# Power.net
KiCad netlist of a schematic drawn in Altium Designer
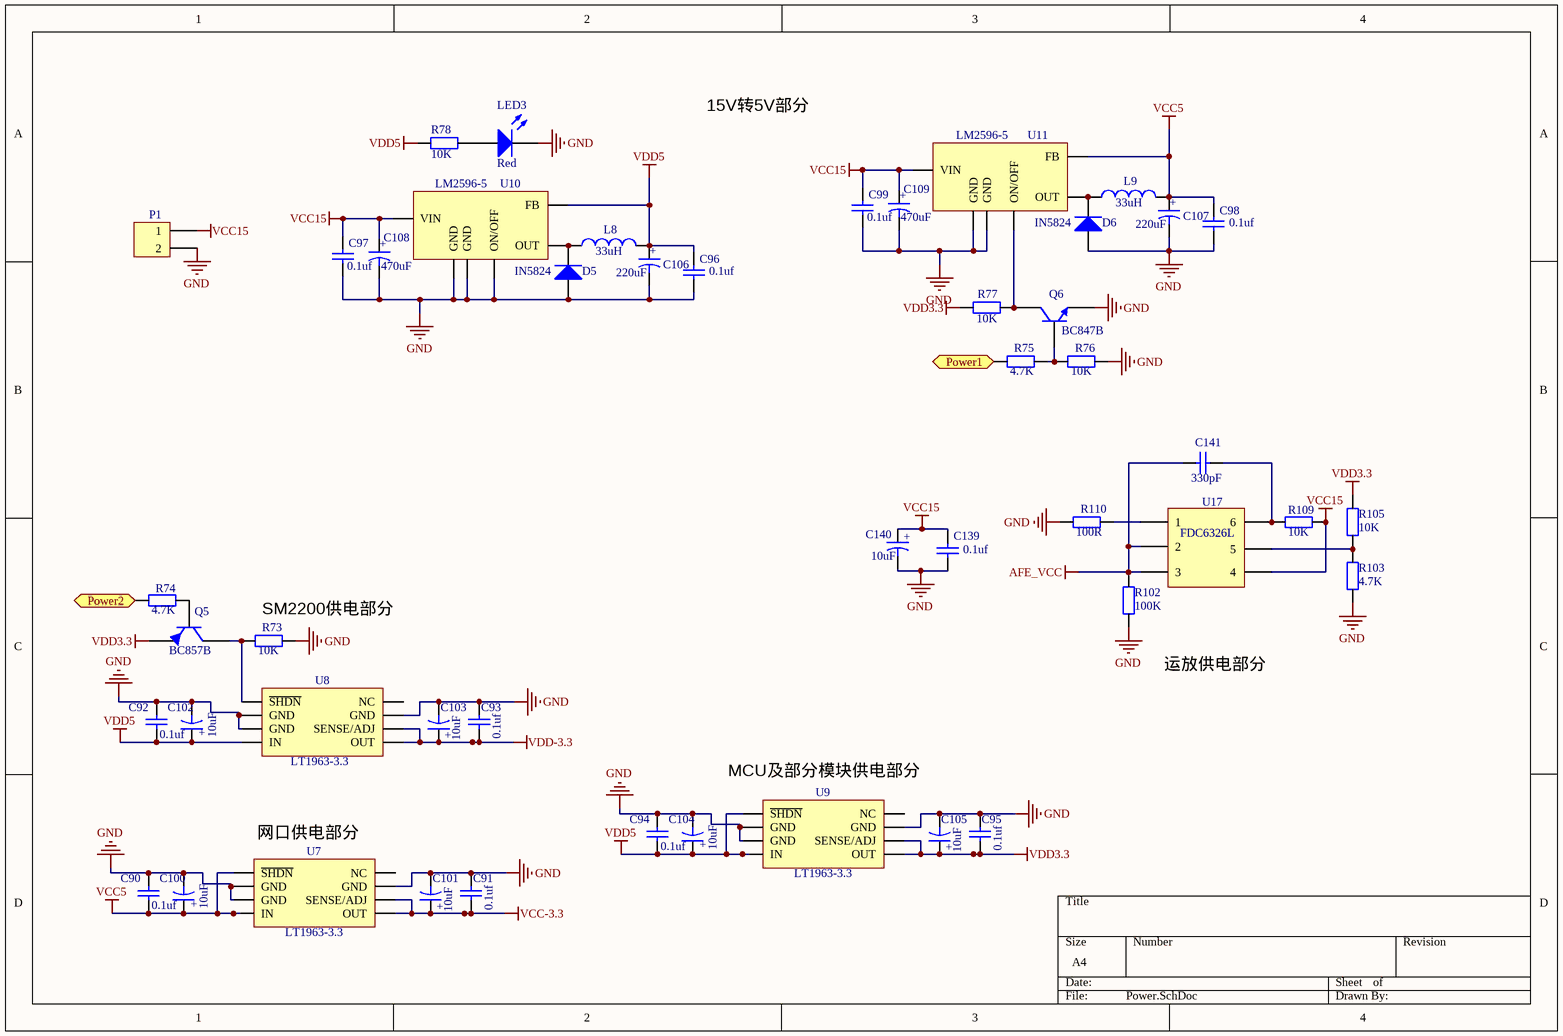
[diagram p0: Power.SchDoc]

(export (version "E")
  (design (tool "Eeschema 10.0.6"))
  (components
    (comp (ref "C90")
      (value "0.1uf")
      (footprint "0805")
      (fields (field (name "Comment") "Capacitor-0805"))
      (libsource (lib "集成库—大岐") (part "Capacitor-0805"))
    )
    (comp (ref "C91")
      (value "0.1uf")
      (footprint "0805")
      (fields (field (name "Comment") "Capacitor-0805"))
      (libsource (lib "集成库—大岐") (part "Capacitor-0805"))
    )
    (comp (ref "C92")
      (value "0.1uf")
      (footprint "0805")
      (fields (field (name "Comment") "Capacitor-0805"))
      (libsource (lib "集成库—大岐") (part "Capacitor-0805"))
    )
    (comp (ref "C93")
      (value "0.1uf")
      (footprint "0805")
      (fields (field (name "Comment") "Capacitor-0805"))
      (libsource (lib "集成库—大岐") (part "Capacitor-0805"))
    )
    (comp (ref "C94")
      (value "0.1uf")
      (footprint "0805")
      (fields (field (name "Comment") "Capacitor-0805"))
      (libsource (lib "集成库—大岐") (part "Capacitor-0805"))
    )
    (comp (ref "C95")
      (value "0.1uf")
      (footprint "0805")
      (fields (field (name "Comment") "Capacitor-0805"))
      (libsource (lib "集成库—大岐") (part "Capacitor-0805"))
    )
    (comp (ref "C96")
      (value "0.1uf")
      (footprint "0805")
      (fields (field (name "Comment") "Capacitor-0805"))
      (libsource (lib "集成库—大岐") (part "Capacitor-0805"))
    )
    (comp (ref "C97")
      (value "0.1uf")
      (footprint "0805")
      (fields (field (name "Comment") "Capacitor-0805"))
      (libsource (lib "集成库—大岐") (part "Capacitor-0805"))
    )
    (comp (ref "C98")
      (value "0.1uf")
      (footprint "0805")
      (fields (field (name "Comment") "Capacitor-0805"))
      (libsource (lib "集成库—大岐") (part "Capacitor-0805"))
    )
    (comp (ref "C99")
      (value "0.1uf")
      (footprint "0805")
      (fields (field (name "Comment") "Capacitor-0805"))
      (libsource (lib "集成库—大岐") (part "Capacitor-0805"))
    )
    (comp (ref "C100")
      (value "10uF")
      (footprint "钽电容1206（A3216）")
      (fields (field (name "ALTIUM_UNNAMED_1") "+") (field (name "Comment") "电解电容"))
      (libsource (lib "集成库—大岐") (part "电解电容"))
    )
    (comp (ref "C101")
      (value "10uF")
      (footprint "钽电容1206（A3216）")
      (fields (field (name "ALTIUM_UNNAMED_1") "+") (field (name "Comment") "电解电容"))
      (libsource (lib "集成库—大岐") (part "电解电容"))
    )
    (comp (ref "C102")
      (value "10uF")
      (footprint "钽电容1206（A3216）")
      (fields (field (name "ALTIUM_UNNAMED_1") "+") (field (name "Comment") "电解电容"))
      (libsource (lib "集成库—大岐") (part "电解电容"))
    )
    (comp (ref "C103")
      (value "10uF")
      (footprint "钽电容1206（A3216）")
      (fields (field (name "ALTIUM_UNNAMED_1") "+") (field (name "Comment") "电解电容"))
      (libsource (lib "集成库—大岐") (part "电解电容"))
    )
    (comp (ref "C104")
      (value "10uF")
      (footprint "钽电容1206（A3216）")
      (fields (field (name "ALTIUM_UNNAMED_1") "+") (field (name "Comment") "电解电容"))
      (libsource (lib "集成库—大岐") (part "电解电容"))
    )
    (comp (ref "C105")
      (value "10uF")
      (footprint "钽电容1206（A3216）")
      (fields (field (name "ALTIUM_UNNAMED_1") "+") (field (name "Comment") "电解电容"))
      (libsource (lib "集成库—大岐") (part "电解电容"))
    )
    (comp (ref "C106")
      (value "220uF")
      (footprint "贴片铝电容-8*10.3")
      (fields (field (name "ALTIUM_UNNAMED_1") "+") (field (name "Comment") "电解电容"))
      (libsource (lib "集成库—大岐") (part "电解电容"))
    )
    (comp (ref "C107")
      (value "220uF")
      (footprint "贴片铝电容-8*10.3")
      (fields (field (name "ALTIUM_UNNAMED_1") "+") (field (name "Comment") "电解电容"))
      (libsource (lib "集成库—大岐") (part "电解电容"))
    )
    (comp (ref "C108")
      (value "470uF")
      (footprint "贴片铝电容-10*10")
      (fields (field (name "ALTIUM_UNNAMED_1") "+") (field (name "Comment") "电解电容"))
      (libsource (lib "集成库—大岐") (part "电解电容"))
    )
    (comp (ref "C109")
      (value "470uF")
      (footprint "贴片铝电容-10*10")
      (fields (field (name "ALTIUM_UNNAMED_1") "+") (field (name "Comment") "电解电容"))
      (libsource (lib "集成库—大岐") (part "电解电容"))
    )
    (comp (ref "C139")
      (value "0.1uf")
      (footprint "0805")
      (fields (field (name "Comment") "Capacitor-0805"))
      (libsource (lib "集成库—大岐") (part "Capacitor-0805"))
    )
    (comp (ref "C140")
      (value "10uF")
      (footprint "3528")
      (fields (field (name "ALTIUM_UNNAMED_1") "+") (field (name "Comment") "电解电容"))
      (libsource (lib "原理图库") (part "电解电容"))
    )
    (comp (ref "C141")
      (value "330pF")
      (footprint "0603")
      (fields (field (name "Comment") "Capacitor-0805"))
      (libsource (lib "集成库—大岐") (part "Capacitor-0805"))
    )
    (comp (ref "D5")
      (value "IN5824")
      (footprint "IN5824")
      (fields (field (name "ALTIUM_UNNAMED_1") "IN5824"))
      (libsource (lib "集成库—大岐") (part "IN5824"))
    )
    (comp (ref "D6")
      (value "IN5824")
      (footprint "IN5824")
      (fields (field (name "ALTIUM_UNNAMED_1") "IN5824"))
      (libsource (lib "集成库—大岐") (part "IN5824"))
    )
    (comp (ref "L8")
      (value "33uH")
      (footprint "SLF6025   电感")
      (fields (field (name "Comment") "Inductor"))
      (libsource (lib "集成库—大岐") (part "Inductor"))
    )
    (comp (ref "L9")
      (value "33uH")
      (footprint "SLF6025   电感")
      (fields (field (name "Comment") "Inductor"))
      (libsource (lib "集成库—大岐") (part "Inductor"))
    )
    (comp (ref "LED3")
      (value "LED")
      (footprint "外插小灯")
      (fields (field (name "COLOR") "Red"))
      (libsource (lib "原理图库") (part "LED"))
    )
    (comp (ref "P1") (value "端子2") (footprint "MOLEX-2") (libsource (lib "原理图库") (part "端子2")))
    (comp (ref "Q5")
      (value "BC587B")
      (footprint "BC847B")
      (fields (field (name "NAME") "BC857B"))
      (libsource (lib "原理图库") (part "BC587B"))
    )
    (comp (ref "Q6")
      (value "BC847")
      (footprint "BC847B")
      (fields (field (name "NAME") "BC847B"))
      (libsource (lib "原理图库") (part "BC847"))
    )
    (comp (ref "R73")
      (value "10K")
      (footprint "0603")
      (fields (field (name "Comment") "Resistor-0603"))
      (libsource (lib "原理图库") (part "Resistor-0603"))
    )
    (comp (ref "R74")
      (value "4.7K")
      (footprint "0603")
      (fields (field (name "Comment") "Resistor-0603"))
      (libsource (lib "原理图库") (part "Resistor-0603"))
    )
    (comp (ref "R75")
      (value "4.7K")
      (footprint "0603")
      (fields (field (name "Comment") "Resistor-0603"))
      (libsource (lib "原理图库") (part "Resistor-0603"))
    )
    (comp (ref "R76")
      (value "10K")
      (footprint "0603")
      (fields (field (name "Comment") "Resistor-0603"))
      (libsource (lib "原理图库") (part "Resistor-0603"))
    )
    (comp (ref "R77")
      (value "10K")
      (footprint "0603")
      (fields (field (name "Comment") "Resistor-0603"))
      (libsource (lib "") (part "Resistor-0603_2"))
    )
    (comp (ref "R78")
      (value "10K")
      (footprint "0603")
      (fields (field (name "Comment") "Resistor-0603"))
      (libsource (lib "原理图库") (part "Resistor-0603"))
    )
    (comp (ref "R102")
      (value "100K")
      (footprint "0603")
      (fields (field (name "Comment") "Resistor-0603"))
      (libsource (lib "") (part "Resistor-0603_1"))
    )
    (comp (ref "R103")
      (value "4.7K")
      (footprint "0603")
      (fields (field (name "Comment") "Resistor-0603"))
      (libsource (lib "") (part "Resistor-0603_1"))
    )
    (comp (ref "R105")
      (value "10K")
      (footprint "0603")
      (fields (field (name "Comment") "Resistor-0603"))
      (libsource (lib "") (part "Resistor-0603_1"))
    )
    (comp (ref "R109")
      (value "10K")
      (footprint "0603")
      (fields (field (name "Comment") "Resistor-0603"))
      (libsource (lib "原理图库") (part "Resistor-0603"))
    )
    (comp (ref "R110")
      (value "100R")
      (footprint "0603")
      (fields (field (name "Comment") "Resistor-0603"))
      (libsource (lib "") (part "Resistor-0603_2"))
    )
    (comp (ref "U7")
      (value "LT1963")
      (footprint "LT1963")
      (fields (field (name "ALTIUM_UNNAMED_1") "LT1963-3.3"))
      (libsource (lib "集成库—大岐") (part "LT1963"))
    )
    (comp (ref "U8")
      (value "LT1963")
      (footprint "LT1963")
      (fields (field (name "ALTIUM_UNNAMED_1") "LT1963-3.3"))
      (libsource (lib "集成库—大岐") (part "LT1963"))
    )
    (comp (ref "U9")
      (value "LT1963")
      (footprint "LT1963")
      (fields (field (name "ALTIUM_UNNAMED_1") "LT1963-3.3"))
      (libsource (lib "集成库—大岐") (part "LT1963"))
    )
    (comp (ref "U10")
      (value "LM2596")
      (footprint "LM2596")
      (fields (field (name "ALTIUM_UNNAMED_1") "LM2596-5"))
      (libsource (lib "集成库—大岐") (part "LM2596"))
    )
    (comp (ref "U11")
      (value "LM2596")
      (footprint "LM2596")
      (fields (field (name "ALTIUM_UNNAMED_1") "LM2596-5"))
      (libsource (lib "集成库—大岐") (part "LM2596"))
    )
    (comp (ref "U17")
      (value "FDC6326L")
      (footprint "FDC6326L")
      (fields (field (name "NAME") "FDC6326L"))
      (libsource (lib "原理图库") (part "FDC6326L"))
    )
  )
  (nets
    (net (code "1") (name "/Power1") (class "Default")
      (node (ref "R75") (pin "2") (pinfunction "2_2") (pintype "passive"))
    )
    (net (code "2") (name "/Power2") (class "Default")
      (node (ref "R74") (pin "2") (pinfunction "2_2") (pintype "passive"))
    )
    (net (code "3") (name "AFE_VCC") (class "Default")
      (node (ref "C141") (pin "2") (pinfunction "2_2") (pintype "passive"))
      (node (ref "R102") (pin "2") (pinfunction "2_2") (pintype "passive"))
      (node (ref "U17") (pin "2") (pinfunction "2_2") (pintype "passive"))
      (node (ref "U17") (pin "3") (pinfunction "3_3") (pintype "passive"))
    )
    (net (code "4") (name "GND") (class "Default")
      (node (ref "C100") (pin "1") (pinfunction "1_1") (pintype "passive"))
      (node (ref "C101") (pin "1") (pinfunction "1_1") (pintype "passive"))
      (node (ref "C102") (pin "1") (pinfunction "1_1") (pintype "passive"))
      (node (ref "C103") (pin "1") (pinfunction "1_1") (pintype "passive"))
      (node (ref "C104") (pin "1") (pinfunction "1_1") (pintype "passive"))
      (node (ref "C105") (pin "1") (pinfunction "1_1") (pintype "passive"))
      (node (ref "C106") (pin "1") (pinfunction "1_1") (pintype "passive"))
      (node (ref "C107") (pin "1") (pinfunction "1_1") (pintype "passive"))
      (node (ref "C108") (pin "1") (pinfunction "1_1") (pintype "passive"))
      (node (ref "C109") (pin "1") (pinfunction "1_1") (pintype "passive"))
      (node (ref "C139") (pin "1") (pinfunction "1_1") (pintype "passive"))
      (node (ref "C140") (pin "1") (pinfunction "1_1") (pintype "passive"))
      (node (ref "C90") (pin "2") (pinfunction "2_2") (pintype "passive"))
      (node (ref "C91") (pin "2") (pinfunction "2_2") (pintype "passive"))
      (node (ref "C92") (pin "2") (pinfunction "2_2") (pintype "passive"))
      (node (ref "C93") (pin "2") (pinfunction "2_2") (pintype "passive"))
      (node (ref "C94") (pin "2") (pinfunction "2_2") (pintype "passive"))
      (node (ref "C95") (pin "2") (pinfunction "2_2") (pintype "passive"))
      (node (ref "C96") (pin "1") (pinfunction "1_1") (pintype "passive"))
      (node (ref "C97") (pin "1") (pinfunction "1_1") (pintype "passive"))
      (node (ref "C98") (pin "1") (pinfunction "1_1") (pintype "passive"))
      (node (ref "C99") (pin "1") (pinfunction "1_1") (pintype "passive"))
      (node (ref "D5") (pin "1") (pinfunction "A_1") (pintype "passive"))
      (node (ref "D6") (pin "1") (pinfunction "A_1") (pintype "passive"))
      (node (ref "LED3") (pin "2") (pinfunction "2_2") (pintype "passive"))
      (node (ref "P1") (pin "2") (pinfunction "2_2") (pintype "passive"))
      (node (ref "Q6") (pin "1") (pinfunction "E_1") (pintype "passive"))
      (node (ref "R102") (pin "1") (pinfunction "1_1") (pintype "passive"))
      (node (ref "R103") (pin "1") (pinfunction "1_1") (pintype "passive"))
      (node (ref "R110") (pin "1") (pinfunction "1_1") (pintype "passive"))
      (node (ref "R73") (pin "1") (pinfunction "1_1") (pintype "passive"))
      (node (ref "R76") (pin "1") (pinfunction "1_1") (pintype "passive"))
      (node (ref "U10") (pin "3") (pinfunction "GND_3") (pintype "passive"))
      (node (ref "U10") (pin "5") (pinfunction "ON/OFF_5") (pintype "passive"))
      (node (ref "U10") (pin "6") (pinfunction "GND_6") (pintype "passive"))
      (node (ref "U11") (pin "3") (pinfunction "GND_3") (pintype "passive"))
      (node (ref "U11") (pin "6") (pinfunction "GND_6") (pintype "passive"))
      (node (ref "U7") (pin "3") (pinfunction "GND_3") (pintype "passive"))
      (node (ref "U7") (pin "6") (pinfunction "GND_6") (pintype "passive"))
      (node (ref "U7") (pin "7") (pinfunction "GND_7") (pintype "passive"))
      (node (ref "U8") (pin "3") (pinfunction "GND_3") (pintype "passive"))
      (node (ref "U8") (pin "6") (pinfunction "GND_6") (pintype "passive"))
      (node (ref "U8") (pin "7") (pinfunction "GND_7") (pintype "passive"))
      (node (ref "U9") (pin "3") (pinfunction "GND_3") (pintype "passive"))
      (node (ref "U9") (pin "6") (pinfunction "GND_6") (pintype "passive"))
      (node (ref "U9") (pin "7") (pinfunction "GND_7") (pintype "passive"))
    )
    (net (code "5") (name "Net-(C141-Pad1)") (class "Default")
      (node (ref "C141") (pin "1") (pinfunction "1_1") (pintype "passive"))
      (node (ref "R109") (pin "2") (pinfunction "2_2") (pintype "passive"))
      (node (ref "U17") (pin "6") (pinfunction "6_6") (pintype "passive"))
    )
    (net (code "6") (name "Net-(D5-K)") (class "Default")
      (node (ref "D5") (pin "2") (pinfunction "K_2") (pintype "passive"))
      (node (ref "L8") (pin "1") (pinfunction "1_1") (pintype "passive"))
      (node (ref "U10") (pin "2") (pinfunction "OUT_2") (pintype "passive"))
    )
    (net (code "7") (name "Net-(D6-K)") (class "Default")
      (node (ref "D6") (pin "2") (pinfunction "K_2") (pintype "passive"))
      (node (ref "L9") (pin "1") (pinfunction "1_1") (pintype "passive"))
      (node (ref "U11") (pin "2") (pinfunction "OUT_2") (pintype "passive"))
    )
    (net (code "8") (name "Net-(LED3-A)") (class "Default")
      (node (ref "LED3") (pin "1") (pinfunction "A_1") (pintype "passive"))
      (node (ref "R78") (pin "1") (pinfunction "1_1") (pintype "passive"))
    )
    (net (code "9") (name "Net-(Q5-B)") (class "Default")
      (node (ref "Q5") (pin "2") (pinfunction "B_2") (pintype "passive"))
      (node (ref "R74") (pin "1") (pinfunction "1_1") (pintype "passive"))
    )
    (net (code "10") (name "Net-(Q5-C)") (class "Default")
      (node (ref "Q5") (pin "3") (pinfunction "C_3") (pintype "passive"))
      (node (ref "R73") (pin "2") (pinfunction "2_2") (pintype "passive"))
      (node (ref "U8") (pin "5") (pinfunction "~{SHDN}_5") (pintype "passive"))
    )
    (net (code "11") (name "Net-(Q6-B)") (class "Default")
      (node (ref "Q6") (pin "2") (pinfunction "B_2") (pintype "passive"))
      (node (ref "R75") (pin "1") (pinfunction "1_1") (pintype "passive"))
      (node (ref "R76") (pin "2") (pinfunction "2_2") (pintype "passive"))
    )
    (net (code "12") (name "Net-(Q6-C)") (class "Default")
      (node (ref "Q6") (pin "3") (pinfunction "C_3") (pintype "passive"))
      (node (ref "R77") (pin "2") (pinfunction "2_2") (pintype "passive"))
      (node (ref "U11") (pin "5") (pinfunction "ON/OFF_5") (pintype "passive"))
    )
    (net (code "13") (name "Net-(R103-Pad2)") (class "Default")
      (node (ref "R103") (pin "2") (pinfunction "2_2") (pintype "passive"))
      (node (ref "R105") (pin "1") (pinfunction "1_1") (pintype "passive"))
      (node (ref "U17") (pin "5") (pinfunction "5_5") (pintype "passive"))
    )
    (net (code "14") (name "Net-(R110-Pad2)") (class "Default")
      (node (ref "R110") (pin "2") (pinfunction "2_2") (pintype "passive"))
      (node (ref "U17") (pin "1") (pinfunction "1_1") (pintype "passive"))
    )
    (net (code "15") (name "VCC-3.3") (class "Default")
      (node (ref "C101") (pin "2") (pinfunction "2_2") (pintype "passive"))
      (node (ref "C91") (pin "1") (pinfunction "1_1") (pintype "passive"))
      (node (ref "U7") (pin "1") (pinfunction "OUT_1") (pintype "passive"))
      (node (ref "U7") (pin "2") (pinfunction "SENSE/ADJ_2") (pintype "passive"))
    )
    (net (code "16") (name "VCC5") (class "Default")
      (node (ref "C100") (pin "2") (pinfunction "2_2") (pintype "passive"))
      (node (ref "C107") (pin "2") (pinfunction "2_2") (pintype "passive"))
      (node (ref "C90") (pin "1") (pinfunction "1_1") (pintype "passive"))
      (node (ref "C98") (pin "2") (pinfunction "2_2") (pintype "passive"))
      (node (ref "L9") (pin "2") (pinfunction "2_2") (pintype "passive"))
      (node (ref "U11") (pin "4") (pinfunction "FB_4") (pintype "passive"))
      (node (ref "U7") (pin "5") (pinfunction "~{SHDN}_5") (pintype "passive"))
      (node (ref "U7") (pin "8") (pinfunction "IN_8") (pintype "passive"))
    )
    (net (code "17") (name "VCC15") (class "Default")
      (node (ref "C108") (pin "2") (pinfunction "2_2") (pintype "passive"))
      (node (ref "C109") (pin "2") (pinfunction "2_2") (pintype "passive"))
      (node (ref "C139") (pin "2") (pinfunction "2_2") (pintype "passive"))
      (node (ref "C140") (pin "2") (pinfunction "2_2") (pintype "passive"))
      (node (ref "C97") (pin "2") (pinfunction "2_2") (pintype "passive"))
      (node (ref "C99") (pin "2") (pinfunction "2_2") (pintype "passive"))
      (node (ref "P1") (pin "1") (pinfunction "1_1") (pintype "passive"))
      (node (ref "R109") (pin "1") (pinfunction "1_1") (pintype "passive"))
      (node (ref "U10") (pin "1") (pinfunction "VIN_1") (pintype "passive"))
      (node (ref "U11") (pin "1") (pinfunction "VIN_1") (pintype "passive"))
      (node (ref "U17") (pin "4") (pinfunction "4_4") (pintype "passive"))
    )
    (net (code "18") (name "VDD-3.3") (class "Default")
      (node (ref "C103") (pin "2") (pinfunction "2_2") (pintype "passive"))
      (node (ref "C93") (pin "1") (pinfunction "1_1") (pintype "passive"))
      (node (ref "U8") (pin "1") (pinfunction "OUT_1") (pintype "passive"))
      (node (ref "U8") (pin "2") (pinfunction "SENSE/ADJ_2") (pintype "passive"))
    )
    (net (code "19") (name "VDD3.3") (class "Default")
      (node (ref "C105") (pin "2") (pinfunction "2_2") (pintype "passive"))
      (node (ref "C95") (pin "1") (pinfunction "1_1") (pintype "passive"))
      (node (ref "Q5") (pin "1") (pinfunction "E_1") (pintype "passive"))
      (node (ref "R105") (pin "2") (pinfunction "2_2") (pintype "passive"))
      (node (ref "R77") (pin "1") (pinfunction "1_1") (pintype "passive"))
      (node (ref "U9") (pin "1") (pinfunction "OUT_1") (pintype "passive"))
      (node (ref "U9") (pin "2") (pinfunction "SENSE/ADJ_2") (pintype "passive"))
    )
    (net (code "20") (name "VDD5") (class "Default")
      (node (ref "C102") (pin "2") (pinfunction "2_2") (pintype "passive"))
      (node (ref "C104") (pin "2") (pinfunction "2_2") (pintype "passive"))
      (node (ref "C106") (pin "2") (pinfunction "2_2") (pintype "passive"))
      (node (ref "C92") (pin "1") (pinfunction "1_1") (pintype "passive"))
      (node (ref "C94") (pin "1") (pinfunction "1_1") (pintype "passive"))
      (node (ref "C96") (pin "2") (pinfunction "2_2") (pintype "passive"))
      (node (ref "L8") (pin "2") (pinfunction "2_2") (pintype "passive"))
      (node (ref "R78") (pin "2") (pinfunction "2_2") (pintype "passive"))
      (node (ref "U10") (pin "4") (pinfunction "FB_4") (pintype "passive"))
      (node (ref "U8") (pin "8") (pinfunction "IN_8") (pintype "passive"))
      (node (ref "U9") (pin "5") (pinfunction "~{SHDN}_5") (pintype "passive"))
      (node (ref "U9") (pin "8") (pinfunction "IN_8") (pintype "passive"))
    )
    (net (code "21") (name "unconnected-(U7-NC-Pad4)") (class "Default")
      (node (ref "U7") (pin "4") (pinfunction "NC_4") (pintype "passive"))
    )
    (net (code "22") (name "unconnected-(U8-NC-Pad4)") (class "Default")
      (node (ref "U8") (pin "4") (pinfunction "NC_4") (pintype "passive"))
    )
    (net (code "23") (name "unconnected-(U9-NC-Pad4)") (class "Default")
      (node (ref "U9") (pin "4") (pinfunction "NC_4") (pintype "passive"))
    )
  )
)
